# IV_Swinger_2_module.net
KiCad netlist of a schematic drawn in EAGLE
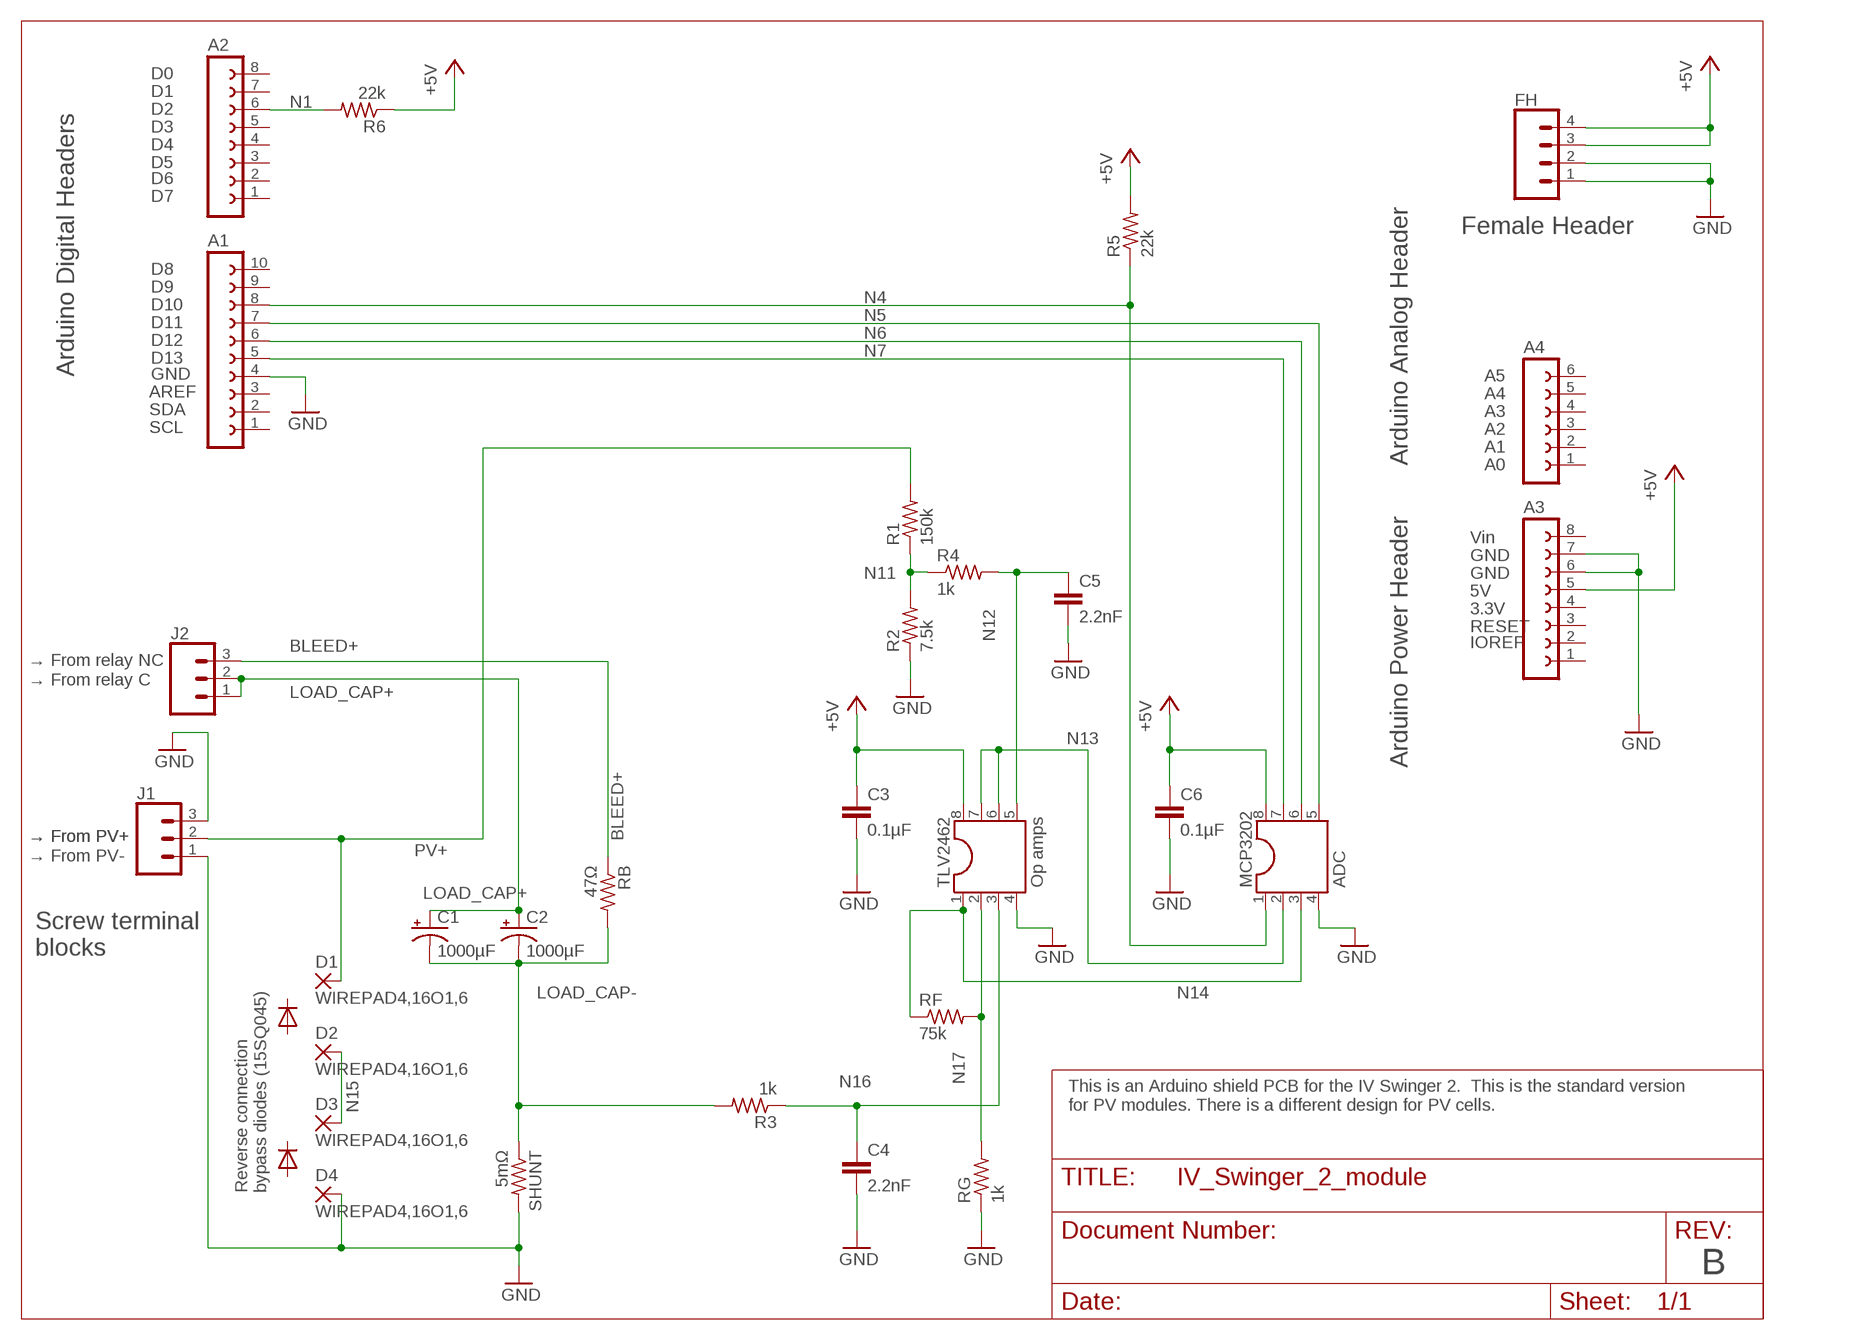
[diagram p0: schematic, sheet 1]

(export (version "E")
  (design (tool "Eeschema 10.0.6"))
  (components
    (comp (ref "A1")
      (value "FE10-1")
      (footprint "eagle-import:FE10")
      (libsource (lib "eagle-import") (part "FE10-1"))
    )
    (comp (ref "A2")
      (value "FE08-1")
      (footprint "eagle-import:FE08")
      (libsource (lib "eagle-import") (part "FE08-1"))
    )
    (comp (ref "A3")
      (value "FE08-1")
      (footprint "eagle-import:FE08")
      (libsource (lib "eagle-import") (part "FE08-1"))
    )
    (comp (ref "A4")
      (value "FE06-1")
      (footprint "eagle-import:FE06")
      (libsource (lib "eagle-import") (part "FE06-1"))
    )
    (comp (ref "C1")
      (value "1000µF")
      (footprint "eagle-import:E7,5-18")
      (libsource (lib "eagle-import") (part "CPOL-USE7.5-18"))
    )
    (comp (ref "C2")
      (value "1000µF")
      (footprint "eagle-import:E7,5-18")
      (libsource (lib "eagle-import") (part "CPOL-USE7.5-18"))
    )
    (comp (ref "C3")
      (value "0.1µF")
      (footprint "eagle-import:C025-030X050")
      (libsource (lib "eagle-import") (part "C-EU025-030X050"))
    )
    (comp (ref "C4")
      (value "2.2nF")
      (footprint "eagle-import:C025-030X050")
      (libsource (lib "eagle-import") (part "C-EU025-030X050"))
    )
    (comp (ref "C5")
      (value "2.2nF")
      (footprint "eagle-import:C025-030X050")
      (libsource (lib "eagle-import") (part "C-EU025-030X050"))
    )
    (comp (ref "C6")
      (value "0.1µF")
      (footprint "eagle-import:C025-030X050")
      (libsource (lib "eagle-import") (part "C-EU025-030X050"))
    )
    (comp (ref "D1")
      (value "WIREPAD4,16O1,6")
      (footprint "eagle-import:4,16O1,6")
      (fields (field (name "SPICEPREFIX") "X"))
      (libsource (lib "eagle-import") (part "WIREPAD4,16O1,6"))
    )
    (comp (ref "D2")
      (value "WIREPAD4,16O1,6")
      (footprint "eagle-import:4,16O1,6")
      (libsource (lib "eagle-import") (part "WIREPAD4,16O1,6"))
    )
    (comp (ref "D3")
      (value "WIREPAD4,16O1,6")
      (footprint "eagle-import:4,16O1,6")
      (libsource (lib "eagle-import") (part "WIREPAD4,16O1,6"))
    )
    (comp (ref "D4")
      (value "WIREPAD4,16O1,6")
      (footprint "eagle-import:4,16O1,6")
      (libsource (lib "eagle-import") (part "WIREPAD4,16O1,6"))
    )
    (comp (ref "FH")
      (value "CONN_04LONGPADS")
      (footprint "eagle-import:1X04_LONGPADS")
      (libsource (lib "eagle-import") (part "CONN_04LONGPADS"))
    )
    (comp (ref "J1")
      (value "CONN_03-SCREW-5MM")
      (footprint "eagle-import:SCREWTERMINAL-5MM-3")
      (libsource (lib "eagle-import") (part "CONN_03-SCREW-5MM"))
    )
    (comp (ref "J2")
      (value "CONN_03-SCREW-5MM")
      (footprint "eagle-import:SCREWTERMINAL-5MM-3")
      (libsource (lib "eagle-import") (part "CONN_03-SCREW-5MM"))
    )
    (comp (ref "MCP3202")
      (value "ADC")
      (footprint "eagle-import:SOCKET-08")
      (libsource (lib "eagle-import") (part "DIL8S"))
    )
    (comp (ref "R1")
      (value "150k")
      (footprint "eagle-import:0207_10")
      (libsource (lib "eagle-import") (part "R-US_0207/10"))
    )
    (comp (ref "R2")
      (value "7.5k")
      (footprint "eagle-import:0207_10")
      (libsource (lib "eagle-import") (part "R-US_0207/10"))
    )
    (comp (ref "R3")
      (value "1k")
      (footprint "eagle-import:0207_10")
      (libsource (lib "eagle-import") (part "R-US_0207/10"))
    )
    (comp (ref "R4")
      (value "1k")
      (footprint "eagle-import:0207_10")
      (libsource (lib "eagle-import") (part "R-US_0207/10"))
    )
    (comp (ref "R5")
      (value "22k")
      (footprint "eagle-import:0207_10")
      (libsource (lib "eagle-import") (part "R-US_0207/10"))
    )
    (comp (ref "R6")
      (value "22k")
      (footprint "eagle-import:0207_10")
      (libsource (lib "eagle-import") (part "R-US_0207/10"))
    )
    (comp (ref "RB")
      (value "47Ω")
      (footprint "eagle-import:P0817V")
      (libsource (lib "eagle-import") (part "R-US_0817/7V"))
    )
    (comp (ref "RF")
      (value "75k")
      (footprint "eagle-import:0207_10")
      (libsource (lib "eagle-import") (part "R-US_0207/10"))
    )
    (comp (ref "RG")
      (value "1k")
      (footprint "eagle-import:0207_10")
      (libsource (lib "eagle-import") (part "R-US_0207/10"))
    )
    (comp (ref "SHUNT")
      (value "5mΩ")
      (footprint "eagle-import:0617V")
      (libsource (lib "eagle-import") (part "R-US_0617/5V"))
    )
    (comp (ref "TLV2462")
      (value "Op amps")
      (footprint "eagle-import:SOCKET-08")
      (libsource (lib "eagle-import") (part "DIL8S"))
    )
  )
  (nets
    (net (code "1") (name "+5V") (class "Default")
      (node (ref "A3") (pin "5") (pinfunction "5_5") (pintype "passive"))
      (node (ref "C3") (pin "1") (pinfunction "1_1") (pintype "passive"))
      (node (ref "C6") (pin "1") (pinfunction "1_1") (pintype "passive"))
      (node (ref "FH") (pin "3") (pinfunction "3_3") (pintype "passive"))
      (node (ref "FH") (pin "4") (pinfunction "4_4") (pintype "passive"))
      (node (ref "MCP3202") (pin "8") (pinfunction "8_8") (pintype "passive"))
      (node (ref "R5") (pin "2") (pinfunction "2_2") (pintype "passive"))
      (node (ref "R6") (pin "1") (pinfunction "1_1") (pintype "passive"))
      (node (ref "TLV2462") (pin "8") (pinfunction "8_8") (pintype "passive"))
    )
    (net (code "2") (name "/BLEED+") (class "Default")
      (node (ref "J2") (pin "3") (pinfunction "3_3") (pintype "passive"))
      (node (ref "RB") (pin "1") (pinfunction "1_1") (pintype "passive"))
    )
    (net (code "3") (name "/LOAD_CAP+") (class "Default")
      (node (ref "C1") (pin "+") (pinfunction "+_+") (pintype "passive"))
      (node (ref "C2") (pin "+") (pinfunction "+_+") (pintype "passive"))
      (node (ref "J2") (pin "1") (pinfunction "1_1") (pintype "passive"))
      (node (ref "J2") (pin "2") (pinfunction "2_2") (pintype "passive"))
    )
    (net (code "4") (name "/LOAD_CAP-") (class "Default")
      (node (ref "C1") (pin "-") (pinfunction "-_-") (pintype "passive"))
      (node (ref "C2") (pin "-") (pinfunction "-_-") (pintype "passive"))
      (node (ref "R3") (pin "2") (pinfunction "2_2") (pintype "passive"))
      (node (ref "RB") (pin "2") (pinfunction "2_2") (pintype "passive"))
      (node (ref "SHUNT") (pin "1") (pinfunction "1_1") (pintype "passive"))
    )
    (net (code "5") (name "/N1") (class "Default")
      (node (ref "A2") (pin "6") (pinfunction "6_6") (pintype "passive"))
      (node (ref "R6") (pin "2") (pinfunction "2_2") (pintype "passive"))
    )
    (net (code "6") (name "/N4") (class "Default")
      (node (ref "A1") (pin "8") (pinfunction "8_8") (pintype "passive"))
      (node (ref "MCP3202") (pin "1") (pinfunction "1_1") (pintype "passive"))
      (node (ref "R5") (pin "1") (pinfunction "1_1") (pintype "passive"))
    )
    (net (code "7") (name "/N5") (class "Default")
      (node (ref "A1") (pin "7") (pinfunction "7_7") (pintype "passive"))
      (node (ref "MCP3202") (pin "5") (pinfunction "5_5") (pintype "passive"))
    )
    (net (code "8") (name "/N6") (class "Default")
      (node (ref "A1") (pin "6") (pinfunction "6_6") (pintype "passive"))
      (node (ref "MCP3202") (pin "6") (pinfunction "6_6") (pintype "passive"))
    )
    (net (code "9") (name "/N7") (class "Default")
      (node (ref "A1") (pin "5") (pinfunction "5_5") (pintype "passive"))
      (node (ref "MCP3202") (pin "7") (pinfunction "7_7") (pintype "passive"))
    )
    (net (code "10") (name "/N11") (class "Default")
      (node (ref "R1") (pin "1") (pinfunction "1_1") (pintype "passive"))
      (node (ref "R2") (pin "2") (pinfunction "2_2") (pintype "passive"))
      (node (ref "R4") (pin "1") (pinfunction "1_1") (pintype "passive"))
    )
    (net (code "11") (name "/N12") (class "Default")
      (node (ref "C5") (pin "1") (pinfunction "1_1") (pintype "passive"))
      (node (ref "R4") (pin "2") (pinfunction "2_2") (pintype "passive"))
      (node (ref "TLV2462") (pin "5") (pinfunction "5_5") (pintype "passive"))
    )
    (net (code "12") (name "/N13") (class "Default")
      (node (ref "MCP3202") (pin "2") (pinfunction "2_2") (pintype "passive"))
      (node (ref "TLV2462") (pin "6") (pinfunction "6_6") (pintype "passive"))
      (node (ref "TLV2462") (pin "7") (pinfunction "7_7") (pintype "passive"))
    )
    (net (code "13") (name "/N14") (class "Default")
      (node (ref "MCP3202") (pin "3") (pinfunction "3_3") (pintype "passive"))
      (node (ref "RF") (pin "1") (pinfunction "1_1") (pintype "passive"))
      (node (ref "TLV2462") (pin "1") (pinfunction "1_1") (pintype "passive"))
    )
    (net (code "14") (name "/N15") (class "Default")
      (node (ref "D2") (pin "1") (pinfunction "P_1") (pintype "passive"))
      (node (ref "D3") (pin "1") (pinfunction "P_1") (pintype "passive"))
    )
    (net (code "15") (name "/N16") (class "Default")
      (node (ref "C4") (pin "1") (pinfunction "1_1") (pintype "passive"))
      (node (ref "R3") (pin "1") (pinfunction "1_1") (pintype "passive"))
      (node (ref "TLV2462") (pin "3") (pinfunction "3_3") (pintype "passive"))
    )
    (net (code "16") (name "/N17") (class "Default")
      (node (ref "RF") (pin "2") (pinfunction "2_2") (pintype "passive"))
      (node (ref "RG") (pin "2") (pinfunction "2_2") (pintype "passive"))
      (node (ref "TLV2462") (pin "2") (pinfunction "2_2") (pintype "passive"))
    )
    (net (code "17") (name "/PV+") (class "Default")
      (node (ref "D1") (pin "1") (pinfunction "P_1") (pintype "passive"))
      (node (ref "J1") (pin "2") (pinfunction "2_2") (pintype "passive"))
      (node (ref "R1") (pin "2") (pinfunction "2_2") (pintype "passive"))
    )
    (net (code "18") (name "GND") (class "Default")
      (node (ref "A1") (pin "4") (pinfunction "4_4") (pintype "passive"))
      (node (ref "A3") (pin "6") (pinfunction "6_6") (pintype "passive"))
      (node (ref "A3") (pin "7") (pinfunction "7_7") (pintype "passive"))
      (node (ref "C3") (pin "2") (pinfunction "2_2") (pintype "passive"))
      (node (ref "C4") (pin "2") (pinfunction "2_2") (pintype "passive"))
      (node (ref "C5") (pin "2") (pinfunction "2_2") (pintype "passive"))
      (node (ref "C6") (pin "2") (pinfunction "2_2") (pintype "passive"))
      (node (ref "D4") (pin "1") (pinfunction "P_1") (pintype "passive"))
      (node (ref "FH") (pin "1") (pinfunction "1_1") (pintype "passive"))
      (node (ref "FH") (pin "2") (pinfunction "2_2") (pintype "passive"))
      (node (ref "J1") (pin "1") (pinfunction "1_1") (pintype "passive"))
      (node (ref "J1") (pin "3") (pinfunction "3_3") (pintype "passive"))
      (node (ref "MCP3202") (pin "4") (pinfunction "4_4") (pintype "passive"))
      (node (ref "R2") (pin "1") (pinfunction "1_1") (pintype "passive"))
      (node (ref "RG") (pin "1") (pinfunction "1_1") (pintype "passive"))
      (node (ref "SHUNT") (pin "2") (pinfunction "2_2") (pintype "passive"))
      (node (ref "TLV2462") (pin "4") (pinfunction "4_4") (pintype "passive"))
    )
    (net (code "19") (name "unconnected-(A1-Pad1)") (class "Default")
      (node (ref "A1") (pin "1") (pinfunction "1_1") (pintype "passive"))
    )
    (net (code "20") (name "unconnected-(A1-Pad2)") (class "Default")
      (node (ref "A1") (pin "2") (pinfunction "2_2") (pintype "passive"))
    )
    (net (code "21") (name "unconnected-(A1-Pad3)") (class "Default")
      (node (ref "A1") (pin "3") (pinfunction "3_3") (pintype "passive"))
    )
    (net (code "22") (name "unconnected-(A1-Pad9)") (class "Default")
      (node (ref "A1") (pin "9") (pinfunction "9_9") (pintype "passive"))
    )
    (net (code "23") (name "unconnected-(A1-Pad10)") (class "Default")
      (node (ref "A1") (pin "10") (pinfunction "10_10") (pintype "passive"))
    )
    (net (code "24") (name "unconnected-(A2-Pad1)") (class "Default")
      (node (ref "A2") (pin "1") (pinfunction "1_1") (pintype "passive"))
    )
    (net (code "25") (name "unconnected-(A2-Pad2)") (class "Default")
      (node (ref "A2") (pin "2") (pinfunction "2_2") (pintype "passive"))
    )
    (net (code "26") (name "unconnected-(A2-Pad3)") (class "Default")
      (node (ref "A2") (pin "3") (pinfunction "3_3") (pintype "passive"))
    )
    (net (code "27") (name "unconnected-(A2-Pad4)") (class "Default")
      (node (ref "A2") (pin "4") (pinfunction "4_4") (pintype "passive"))
    )
    (net (code "28") (name "unconnected-(A2-Pad5)") (class "Default")
      (node (ref "A2") (pin "5") (pinfunction "5_5") (pintype "passive"))
    )
    (net (code "29") (name "unconnected-(A2-Pad7)") (class "Default")
      (node (ref "A2") (pin "7") (pinfunction "7_7") (pintype "passive"))
    )
    (net (code "30") (name "unconnected-(A2-Pad8)") (class "Default")
      (node (ref "A2") (pin "8") (pinfunction "8_8") (pintype "passive"))
    )
    (net (code "31") (name "unconnected-(A3-Pad1)") (class "Default")
      (node (ref "A3") (pin "1") (pinfunction "1_1") (pintype "passive"))
    )
    (net (code "32") (name "unconnected-(A3-Pad2)") (class "Default")
      (node (ref "A3") (pin "2") (pinfunction "2_2") (pintype "passive"))
    )
    (net (code "33") (name "unconnected-(A3-Pad3)") (class "Default")
      (node (ref "A3") (pin "3") (pinfunction "3_3") (pintype "passive"))
    )
    (net (code "34") (name "unconnected-(A3-Pad4)") (class "Default")
      (node (ref "A3") (pin "4") (pinfunction "4_4") (pintype "passive"))
    )
    (net (code "35") (name "unconnected-(A3-Pad8)") (class "Default")
      (node (ref "A3") (pin "8") (pinfunction "8_8") (pintype "passive"))
    )
    (net (code "36") (name "unconnected-(A4-Pad1)") (class "Default")
      (node (ref "A4") (pin "1") (pinfunction "1_1") (pintype "passive"))
    )
    (net (code "37") (name "unconnected-(A4-Pad2)") (class "Default")
      (node (ref "A4") (pin "2") (pinfunction "2_2") (pintype "passive"))
    )
    (net (code "38") (name "unconnected-(A4-Pad3)") (class "Default")
      (node (ref "A4") (pin "3") (pinfunction "3_3") (pintype "passive"))
    )
    (net (code "39") (name "unconnected-(A4-Pad4)") (class "Default")
      (node (ref "A4") (pin "4") (pinfunction "4_4") (pintype "passive"))
    )
    (net (code "40") (name "unconnected-(A4-Pad5)") (class "Default")
      (node (ref "A4") (pin "5") (pinfunction "5_5") (pintype "passive"))
    )
    (net (code "41") (name "unconnected-(A4-Pad6)") (class "Default")
      (node (ref "A4") (pin "6") (pinfunction "6_6") (pintype "passive"))
    )
  )
)
